# Sheet1.net
KiCad netlist of a schematic drawn in Altium Designer
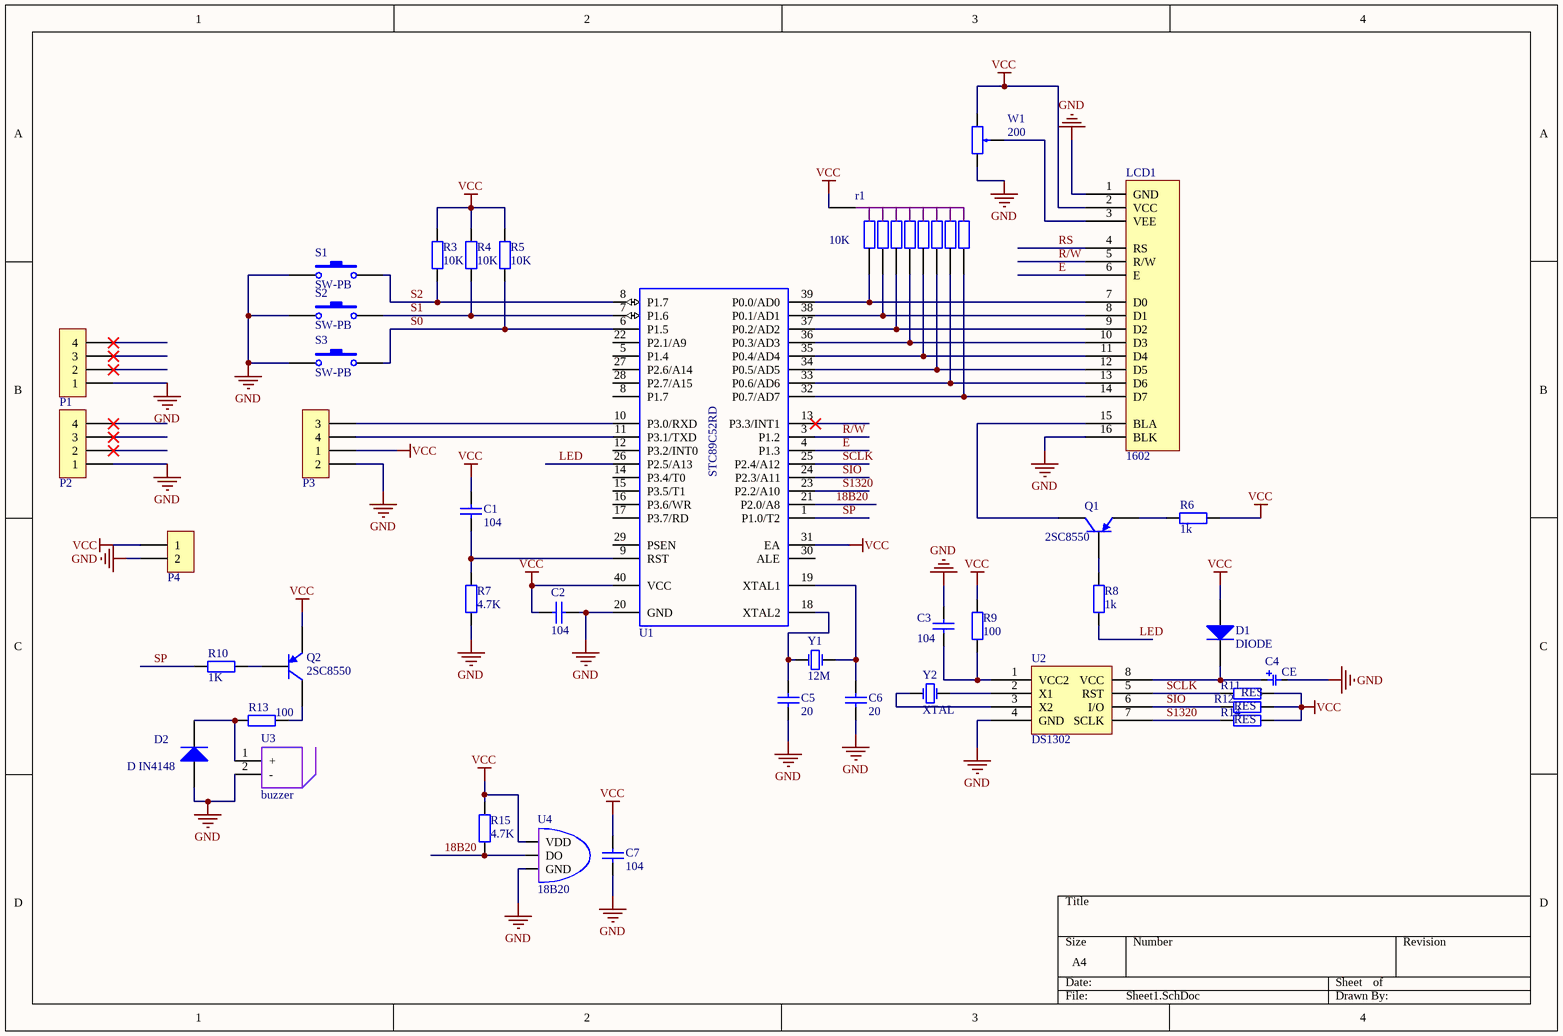
[diagram p0: Sheet1.SchDoc]

(export (version "E")
  (design (tool "Eeschema 10.0.6"))
  (components
    (comp (ref "C1") (value "104") (footprint "0805C") (libsource (lib "ji cheng ku") (part "CAP")))
    (comp (ref "C2") (value "104") (footprint "0805C") (libsource (lib "ji cheng ku") (part "CAP")))
    (comp (ref "C3") (value "104") (footprint "0805C") (libsource (lib "ji cheng ku") (part "CAP")))
    (comp (ref "C4") (value "CE") (footprint "2817c+") (libsource (lib "ji cheng ku") (part "CE")))
    (comp (ref "C5") (value "20") (footprint "0805C") (libsource (lib "ji cheng ku") (part "CAP")))
    (comp (ref "C6") (value "20") (footprint "0805C") (libsource (lib "ji cheng ku") (part "CAP")))
    (comp (ref "C7") (value "104") (footprint "0805C") (libsource (lib "ji cheng ku") (part "CAP")))
    (comp (ref "D1") (value "DIODE") (footprint "SS14-4007") (libsource (lib "ji cheng ku") (part "DIODE")))
    (comp (ref "D2")
      (value "D IN4148")
      (footprint "4148YZ")
      (libsource (lib "ji cheng ku") (part "D IN4148"))
    )
    (comp (ref "LCD1") (value "1602") (footprint "LCD1602") (libsource (lib "chang yong") (part "1602")))
    (comp (ref "P1") (value "CON4") (footprint "sip4") (libsource (lib "LJQ ji cheng ku") (part "CON4")))
    (comp (ref "P2") (value "CON4") (footprint "sip4") (libsource (lib "LJQ ji cheng ku") (part "CON4")))
    (comp (ref "P3") (value "CON4") (footprint "sip4") (libsource (lib "") (part "CON4_1")))
    (comp (ref "P4") (value "CON2") (footprint "SIP2") (libsource (lib "LJQ ji cheng ku") (part "CON2")))
    (comp (ref "Q1") (value "2SC8550") (footprint "SOT23") (libsource (lib "PCB_Project1") (part "2SC8550")))
    (comp (ref "Q2") (value "2SC8550") (footprint "SOT23") (libsource (lib "ji cheng ku") (part "2SC8550")))
    (comp (ref "r1") (value "10K") (footprint "RPZ9") (libsource (lib "ji cheng ku") (part "RPZ9")))
    (comp (ref "R3") (value "10K") (footprint "0805R") (libsource (lib "") (part "RES_1")))
    (comp (ref "R4") (value "10K") (footprint "0805R") (libsource (lib "") (part "RES_1")))
    (comp (ref "R5") (value "10K") (footprint "0805R") (libsource (lib "") (part "RES_1")))
    (comp (ref "R6") (value "1k") (footprint "0805R") (libsource (lib "") (part "RES_1")))
    (comp (ref "R7") (value "4.7K") (footprint "0805R") (libsource (lib "") (part "RES_1")))
    (comp (ref "R8") (value "1k") (footprint "0805R") (libsource (lib "PCB_Project1") (part "RES")))
    (comp (ref "R9") (value "100") (footprint "0805R") (libsource (lib "") (part "RES_1")))
    (comp (ref "R10") (value "1K") (footprint "0805R") (libsource (lib "ji cheng ku") (part "RES")))
    (comp (ref "R11") (value "RES") (footprint "0805R") (libsource (lib "ji cheng ku") (part "RES")))
    (comp (ref "R12") (value "RES") (footprint "0805R") (libsource (lib "ji cheng ku") (part "RES")))
    (comp (ref "R13") (value "100") (footprint "0805R") (libsource (lib "") (part "RES_2")))
    (comp (ref "R14") (value "RES") (footprint "0805R") (libsource (lib "ji cheng ku") (part "RES")))
    (comp (ref "R15") (value "4.7K") (footprint "0805R") (libsource (lib "") (part "RES_1")))
    (comp (ref "S1")
      (value "SW-PB")
      (footprint "SW-AJ24")
      (description "Switch")
      (fields (field (name "PUBLISHER") "Altium Limited"))
      (libsource (lib "ji cheng ku") (part "SW-PB"))
    )
    (comp (ref "S2")
      (value "SW-PB")
      (footprint "SW-AJ24")
      (description "Switch")
      (fields (field (name "PUBLISHER") "Altium Limited"))
      (libsource (lib "ji cheng ku") (part "SW-PB"))
    )
    (comp (ref "S3")
      (value "SW-PB")
      (footprint "SW-AJ24")
      (description "Switch")
      (fields (field (name "PUBLISHER") "Altium Limited"))
      (libsource (lib "ji cheng ku") (part "SW-PB"))
    )
    (comp (ref "U1") (value "STC89C52") (footprint "DIP40") (libsource (lib "ji cheng ku") (part "STC89C52")))
    (comp (ref "U2") (value "DS1302") (footprint "DIP8") (libsource (lib "ji cheng ku") (part "DS1302")))
    (comp (ref "U3") (value "buzzer") (footprint "BUZZER") (libsource (lib "ji cheng ku") (part "buzzer")))
    (comp (ref "U4") (value "18B20") (footprint "18b20") (libsource (lib "ji cheng ku") (part "18B20")))
    (comp (ref "W1")
      (value "200")
      (footprint "RV")
      (description "Variable Resistor")
      (fields (field (name "PUBLISHER") "Altium Limited"))
      (libsource (lib "ji cheng ku") (part "RV"))
    )
    (comp (ref "Y1")
      (value "12M")
      (footprint "XTAL")
      (description "Crystal Oscillator")
      (fields (field (name "PUBLISHER") "Altium Limited"))
      (libsource (lib "ji cheng ku") (part "XTAL"))
    )
    (comp (ref "Y2")
      (value "XTAL")
      (footprint "xtal1-X")
      (description "Crystal Oscillator")
      (fields (field (name "PUBLISHER") "Altium Limited"))
      (libsource (lib "ji cheng ku") (part "XTAL"))
    )
  )
  (nets
    (net (code "1") (name "/18B20") (class "Default")
      (node (ref "R15") (pin "1") (pinfunction "1_1") (pintype "passive"))
      (node (ref "U1") (pin "21") (pinfunction "P2.0/A8_21") (pintype "passive"))
      (node (ref "U4") (pin "2") (pinfunction "DO_2") (pintype "passive"))
    )
    (net (code "2") (name "/E") (class "Default")
      (node (ref "LCD1") (pin "6") (pinfunction "E_6") (pintype "passive"))
      (node (ref "U1") (pin "4") (pinfunction "P1.3_4") (pintype "passive"))
    )
    (net (code "3") (name "/LED") (class "Default")
      (node (ref "R8") (pin "1") (pinfunction "1_1") (pintype "passive"))
      (node (ref "U1") (pin "26") (pinfunction "P2.5/A13_26") (pintype "passive"))
    )
    (net (code "4") (name "/RS") (class "Default")
      (node (ref "LCD1") (pin "4") (pinfunction "RS_4") (pintype "passive"))
    )
    (net (code "5") (name "/R{slash}W") (class "Default")
      (node (ref "LCD1") (pin "5") (pinfunction "R/W_5") (pintype "passive"))
      (node (ref "U1") (pin "3") (pinfunction "P1.2_3") (pintype "passive"))
    )
    (net (code "6") (name "/S0") (class "Default")
      (node (ref "R5") (pin "1") (pinfunction "1_1") (pintype "passive"))
      (node (ref "S3") (pin "2") (pinfunction "2_2") (pintype "passive"))
      (node (ref "U1") (pin "6") (pinfunction "P1.5_6") (pintype "passive"))
    )
    (net (code "7") (name "/S1") (class "Default")
      (node (ref "R4") (pin "1") (pinfunction "1_1") (pintype "passive"))
      (node (ref "S2") (pin "2") (pinfunction "2_2") (pintype "passive"))
      (node (ref "U1") (pin "7") (pinfunction "P1.6_7") (pintype "bidirectional"))
    )
    (net (code "8") (name "/S2") (class "Default")
      (node (ref "R3") (pin "1") (pinfunction "1_1") (pintype "passive"))
      (node (ref "S1") (pin "2") (pinfunction "2_2") (pintype "passive"))
      (node (ref "U1") (pin "8") (pinfunction "P1.7_8") (pintype "bidirectional"))
    )
    (net (code "9") (name "/S1320") (class "Default")
      (node (ref "R14") (pin "1") (pinfunction "1_1") (pintype "passive"))
      (node (ref "U1") (pin "23") (pinfunction "P2.2/A10_23") (pintype "passive"))
      (node (ref "U2") (pin "7") (pinfunction "SCLK_7") (pintype "passive"))
    )
    (net (code "10") (name "/SCLK") (class "Default")
      (node (ref "R11") (pin "1") (pinfunction "1_1") (pintype "passive"))
      (node (ref "U1") (pin "25") (pinfunction "P2.4/A12_25") (pintype "passive"))
      (node (ref "U2") (pin "5") (pinfunction "RST_5") (pintype "passive"))
    )
    (net (code "11") (name "/SIO") (class "Default")
      (node (ref "R12") (pin "1") (pinfunction "1_1") (pintype "passive"))
      (node (ref "U1") (pin "24") (pinfunction "P2.3/A11_24") (pintype "passive"))
      (node (ref "U2") (pin "6") (pinfunction "I/O_6") (pintype "passive"))
    )
    (net (code "12") (name "/SP") (class "Default")
      (node (ref "R10") (pin "1") (pinfunction "1_1") (pintype "passive"))
      (node (ref "U1") (pin "1") (pinfunction "P1.0/T2_1") (pintype "passive"))
    )
    (net (code "13") (name "GND") (class "Default")
      (node (ref "C2") (pin "2") (pinfunction "2_2") (pintype "passive"))
      (node (ref "C3") (pin "2") (pinfunction "2_2") (pintype "passive"))
      (node (ref "C4") (pin "2") (pintype "passive"))
      (node (ref "C5") (pin "1") (pinfunction "1_1") (pintype "passive"))
      (node (ref "C6") (pin "1") (pinfunction "1_1") (pintype "passive"))
      (node (ref "C7") (pin "1") (pinfunction "1_1") (pintype "passive"))
      (node (ref "D2") (pin "1") (pinfunction "A_1") (pintype "passive"))
      (node (ref "LCD1") (pin "1") (pinfunction "GND_1") (pintype "passive"))
      (node (ref "LCD1") (pin "16") (pinfunction "BLK_16") (pintype "passive"))
      (node (ref "P1") (pin "1") (pinfunction "1_1") (pintype "passive"))
      (node (ref "P2") (pin "1") (pinfunction "1_1") (pintype "passive"))
      (node (ref "P3") (pin "2") (pinfunction "2_2") (pintype "passive"))
      (node (ref "P4") (pin "2") (pinfunction "2_2") (pintype "passive"))
      (node (ref "R7") (pin "1") (pinfunction "1_1") (pintype "passive"))
      (node (ref "S1") (pin "1") (pinfunction "1_1") (pintype "passive"))
      (node (ref "S2") (pin "1") (pinfunction "1_1") (pintype "passive"))
      (node (ref "S3") (pin "1") (pinfunction "1_1") (pintype "passive"))
      (node (ref "U1") (pin "20") (pinfunction "GND_20") (pintype "power_in"))
      (node (ref "U2") (pin "4") (pinfunction "GND_4") (pintype "passive"))
      (node (ref "U3") (pin "2") (pinfunction "-_2") (pintype "passive"))
      (node (ref "U4") (pin "1") (pinfunction "GND_1") (pintype "passive"))
      (node (ref "W1") (pin "3") (pinfunction "3_3") (pintype "passive"))
    )
    (net (code "14") (name "Net-(D1-K)") (class "Default")
      (node (ref "C4") (pin "1") (pintype "passive"))
      (node (ref "D1") (pin "2") (pinfunction "K_2") (pintype "passive"))
      (node (ref "U2") (pin "8") (pinfunction "VCC_8") (pintype "passive"))
    )
    (net (code "15") (name "Net-(D2-K)") (class "Default")
      (node (ref "D2") (pin "2") (pinfunction "K_2") (pintype "passive"))
      (node (ref "R13") (pin "2") (pinfunction "2_2") (pintype "passive"))
      (node (ref "U3") (pin "1") (pinfunction "+_1") (pintype "passive"))
    )
    (net (code "16") (name "Net-(LCD1-BLA)") (class "Default")
      (node (ref "LCD1") (pin "15") (pinfunction "BLA_15") (pintype "passive"))
      (node (ref "Q1") (pin "C") (pinfunction "C_C") (pintype "passive"))
    )
    (net (code "17") (name "Net-(LCD1-D0)") (class "Default")
      (node (ref "LCD1") (pin "7") (pinfunction "D0_7") (pintype "passive"))
      (node (ref "U1") (pin "39") (pinfunction "P0.0/AD0_39") (pintype "passive"))
      (node (ref "r1") (pin "2") (pinfunction "2_2") (pintype "passive"))
    )
    (net (code "18") (name "Net-(LCD1-D1)") (class "Default")
      (node (ref "LCD1") (pin "8") (pinfunction "D1_8") (pintype "passive"))
      (node (ref "U1") (pin "38") (pinfunction "P0.1/AD1_38") (pintype "passive"))
      (node (ref "r1") (pin "3") (pinfunction "3_3") (pintype "passive"))
    )
    (net (code "19") (name "Net-(LCD1-D2)") (class "Default")
      (node (ref "LCD1") (pin "9") (pinfunction "D2_9") (pintype "passive"))
      (node (ref "U1") (pin "37") (pinfunction "P0.2/AD2_37") (pintype "passive"))
      (node (ref "r1") (pin "4") (pinfunction "4_4") (pintype "passive"))
    )
    (net (code "20") (name "Net-(LCD1-D3)") (class "Default")
      (node (ref "LCD1") (pin "10") (pinfunction "D3_10") (pintype "passive"))
      (node (ref "U1") (pin "36") (pinfunction "P0.3/AD3_36") (pintype "passive"))
      (node (ref "r1") (pin "5") (pinfunction "5_5") (pintype "passive"))
    )
    (net (code "21") (name "Net-(LCD1-D4)") (class "Default")
      (node (ref "LCD1") (pin "11") (pinfunction "D4_11") (pintype "passive"))
      (node (ref "U1") (pin "35") (pinfunction "P0.4/AD4_35") (pintype "passive"))
      (node (ref "r1") (pin "6") (pinfunction "6_6") (pintype "passive"))
    )
    (net (code "22") (name "Net-(LCD1-D5)") (class "Default")
      (node (ref "LCD1") (pin "12") (pinfunction "D5_12") (pintype "passive"))
      (node (ref "U1") (pin "34") (pinfunction "P0.5/AD5_34") (pintype "passive"))
      (node (ref "r1") (pin "7") (pinfunction "7_7") (pintype "passive"))
    )
    (net (code "23") (name "Net-(LCD1-D6)") (class "Default")
      (node (ref "LCD1") (pin "13") (pinfunction "D6_13") (pintype "passive"))
      (node (ref "U1") (pin "33") (pinfunction "P0.6/AD6_33") (pintype "passive"))
      (node (ref "r1") (pin "8") (pinfunction "8_8") (pintype "passive"))
    )
    (net (code "24") (name "Net-(LCD1-D7)") (class "Default")
      (node (ref "LCD1") (pin "14") (pinfunction "D7_14") (pintype "passive"))
      (node (ref "U1") (pin "32") (pinfunction "P0.7/AD7_32") (pintype "passive"))
      (node (ref "r1") (pin "9") (pinfunction "9_9") (pintype "passive"))
    )
    (net (code "25") (name "Net-(LCD1-VEE)") (class "Default")
      (node (ref "LCD1") (pin "3") (pinfunction "VEE_3") (pintype "passive"))
      (node (ref "W1") (pin "W") (pinfunction "W_W") (pintype "passive"))
    )
    (net (code "26") (name "Net-(Q1-PadB)") (class "Default")
      (node (ref "Q1") (pin "B") (pinfunction "B_B") (pintype "passive"))
      (node (ref "R8") (pin "2") (pinfunction "2_2") (pintype "passive"))
    )
    (net (code "27") (name "Net-(Q1-PadE)") (class "Default")
      (node (ref "Q1") (pin "E") (pinfunction "E_E") (pintype "passive"))
      (node (ref "R6") (pin "2") (pinfunction "2_2") (pintype "passive"))
    )
    (net (code "28") (name "Net-(Q2-PadB)") (class "Default")
      (node (ref "Q2") (pin "B") (pinfunction "B_B") (pintype "passive"))
      (node (ref "R10") (pin "2") (pinfunction "2_2") (pintype "passive"))
    )
    (net (code "29") (name "Net-(Q2-PadC)") (class "Default")
      (node (ref "Q2") (pin "C") (pinfunction "C_C") (pintype "passive"))
      (node (ref "R13") (pin "1") (pinfunction "1_1") (pintype "passive"))
    )
    (net (code "30") (name "Net-(U1-P3.0{slash}RXD)") (class "Default")
      (node (ref "P3") (pin "3") (pinfunction "3_3") (pintype "passive"))
      (node (ref "U1") (pin "10") (pinfunction "P3.0/RXD_10") (pintype "passive"))
    )
    (net (code "31") (name "Net-(U1-P3.1{slash}TXD)") (class "Default")
      (node (ref "P3") (pin "4") (pinfunction "4_4") (pintype "passive"))
      (node (ref "U1") (pin "11") (pinfunction "P3.1/TXD_11") (pintype "passive"))
    )
    (net (code "32") (name "Net-(U1-RST)") (class "Default")
      (node (ref "C1") (pin "1") (pinfunction "1_1") (pintype "passive"))
      (node (ref "R7") (pin "2") (pinfunction "2_2") (pintype "passive"))
      (node (ref "U1") (pin "9") (pinfunction "RST_9") (pintype "passive"))
    )
    (net (code "33") (name "Net-(U1-XTAL1)") (class "Default")
      (node (ref "C6") (pin "2") (pinfunction "2_2") (pintype "passive"))
      (node (ref "U1") (pin "19") (pinfunction "XTAL1_19") (pintype "passive"))
      (node (ref "Y1") (pin "1") (pinfunction "1_1") (pintype "passive"))
    )
    (net (code "34") (name "Net-(U1-XTAL2)") (class "Default")
      (node (ref "C5") (pin "2") (pinfunction "2_2") (pintype "passive"))
      (node (ref "U1") (pin "18") (pinfunction "XTAL2_18") (pintype "passive"))
      (node (ref "Y1") (pin "2") (pinfunction "2_2") (pintype "passive"))
    )
    (net (code "35") (name "Net-(U2-VCC2)") (class "Default")
      (node (ref "C3") (pin "1") (pinfunction "1_1") (pintype "passive"))
      (node (ref "R9") (pin "1") (pinfunction "1_1") (pintype "passive"))
      (node (ref "U2") (pin "1") (pinfunction "VCC2_1") (pintype "passive"))
    )
    (net (code "36") (name "Net-(U2-X1)") (class "Default")
      (node (ref "U2") (pin "2") (pinfunction "X1_2") (pintype "passive"))
      (node (ref "Y2") (pin "2") (pinfunction "2_2") (pintype "passive"))
    )
    (net (code "37") (name "Net-(U2-X2)") (class "Default")
      (node (ref "U2") (pin "3") (pinfunction "X2_3") (pintype "passive"))
      (node (ref "Y2") (pin "1") (pinfunction "1_1") (pintype "passive"))
    )
    (net (code "38") (name "VCC") (class "Default")
      (node (ref "C1") (pin "2") (pinfunction "2_2") (pintype "passive"))
      (node (ref "C2") (pin "1") (pinfunction "1_1") (pintype "passive"))
      (node (ref "C7") (pin "2") (pinfunction "2_2") (pintype "passive"))
      (node (ref "D1") (pin "1") (pinfunction "A_1") (pintype "passive"))
      (node (ref "LCD1") (pin "2") (pinfunction "VCC_2") (pintype "passive"))
      (node (ref "P3") (pin "1") (pinfunction "1_1") (pintype "passive"))
      (node (ref "P4") (pin "1") (pinfunction "1_1") (pintype "passive"))
      (node (ref "Q2") (pin "E") (pinfunction "E_E") (pintype "passive"))
      (node (ref "R11") (pin "2") (pinfunction "2_2") (pintype "passive"))
      (node (ref "R12") (pin "2") (pinfunction "2_2") (pintype "passive"))
      (node (ref "R14") (pin "2") (pinfunction "2_2") (pintype "passive"))
      (node (ref "R15") (pin "2") (pinfunction "2_2") (pintype "passive"))
      (node (ref "R3") (pin "2") (pinfunction "2_2") (pintype "passive"))
      (node (ref "R4") (pin "2") (pinfunction "2_2") (pintype "passive"))
      (node (ref "R5") (pin "2") (pinfunction "2_2") (pintype "passive"))
      (node (ref "R6") (pin "1") (pinfunction "1_1") (pintype "passive"))
      (node (ref "R9") (pin "2") (pinfunction "2_2") (pintype "passive"))
      (node (ref "U1") (pin "31") (pinfunction "EA_31") (pintype "passive"))
      (node (ref "U1") (pin "40") (pinfunction "VCC_40") (pintype "power_in"))
      (node (ref "U4") (pin "3") (pinfunction "VDD_3") (pintype "passive"))
      (node (ref "W1") (pin "1") (pinfunction "1_1") (pintype "passive"))
      (node (ref "r1") (pin "1") (pinfunction "1_1") (pintype "passive"))
    )
    (net (code "39") (name "unconnected-(P1-Pad2)") (class "Default")
      (node (ref "P1") (pin "2") (pinfunction "2_2") (pintype "passive+no_connect"))
    )
    (net (code "40") (name "unconnected-(P1-Pad3)") (class "Default")
      (node (ref "P1") (pin "3") (pinfunction "3_3") (pintype "passive+no_connect"))
    )
    (net (code "41") (name "unconnected-(P1-Pad4)") (class "Default")
      (node (ref "P1") (pin "4") (pinfunction "4_4") (pintype "passive+no_connect"))
    )
    (net (code "42") (name "unconnected-(P2-Pad2)") (class "Default")
      (node (ref "P2") (pin "2") (pinfunction "2_2") (pintype "passive+no_connect"))
    )
    (net (code "43") (name "unconnected-(P2-Pad3)") (class "Default")
      (node (ref "P2") (pin "3") (pinfunction "3_3") (pintype "passive+no_connect"))
    )
    (net (code "44") (name "unconnected-(P2-Pad4)") (class "Default")
      (node (ref "P2") (pin "4") (pinfunction "4_4") (pintype "passive+no_connect"))
    )
    (net (code "45") (name "unconnected-(U1-ALE-Pad30)") (class "Default")
      (node (ref "U1") (pin "30") (pinfunction "ALE_30") (pintype "passive"))
    )
    (net (code "46") (name "unconnected-(U1-P1.4-Pad5)") (class "Default")
      (node (ref "U1") (pin "5") (pinfunction "P1.4_5") (pintype "passive"))
    )
    (net (code "47") (name "unconnected-(U1-P1.7-Pad8)") (class "Default")
      (node (ref "U1") (pin "8") (pinfunction "P1.7_8") (pintype "passive"))
    )
    (net (code "48") (name "unconnected-(U1-P2.1{slash}A9-Pad22)") (class "Default")
      (node (ref "U1") (pin "22") (pinfunction "P2.1/A9_22") (pintype "passive"))
    )
    (net (code "49") (name "unconnected-(U1-P2.6{slash}A14-Pad27)") (class "Default")
      (node (ref "U1") (pin "27") (pinfunction "P2.6/A14_27") (pintype "passive"))
    )
    (net (code "50") (name "unconnected-(U1-P2.7{slash}A15-Pad28)") (class "Default")
      (node (ref "U1") (pin "28") (pinfunction "P2.7/A15_28") (pintype "passive"))
    )
    (net (code "51") (name "unconnected-(U1-P3.2{slash}INT0-Pad12)") (class "Default")
      (node (ref "U1") (pin "12") (pinfunction "P3.2/INT0_12") (pintype "passive"))
    )
    (net (code "52") (name "unconnected-(U1-P3.3{slash}INT1-Pad13)") (class "Default")
      (node (ref "U1") (pin "13") (pinfunction "P3.3/INT1_13") (pintype "passive+no_connect"))
    )
    (net (code "53") (name "unconnected-(U1-P3.4{slash}T0-Pad14)") (class "Default")
      (node (ref "U1") (pin "14") (pinfunction "P3.4/T0_14") (pintype "passive"))
    )
    (net (code "54") (name "unconnected-(U1-P3.5{slash}T1-Pad15)") (class "Default")
      (node (ref "U1") (pin "15") (pinfunction "P3.5/T1_15") (pintype "passive"))
    )
    (net (code "55") (name "unconnected-(U1-P3.6{slash}WR-Pad16)") (class "Default")
      (node (ref "U1") (pin "16") (pinfunction "P3.6/WR_16") (pintype "passive"))
    )
    (net (code "56") (name "unconnected-(U1-P3.7{slash}RD-Pad17)") (class "Default")
      (node (ref "U1") (pin "17") (pinfunction "P3.7/RD_17") (pintype "passive"))
    )
    (net (code "57") (name "unconnected-(U1-PSEN-Pad29)") (class "Default")
      (node (ref "U1") (pin "29") (pinfunction "PSEN_29") (pintype "passive"))
    )
  )
)
